# Output_block.net
KiCad netlist of a schematic drawn in Altium Designer
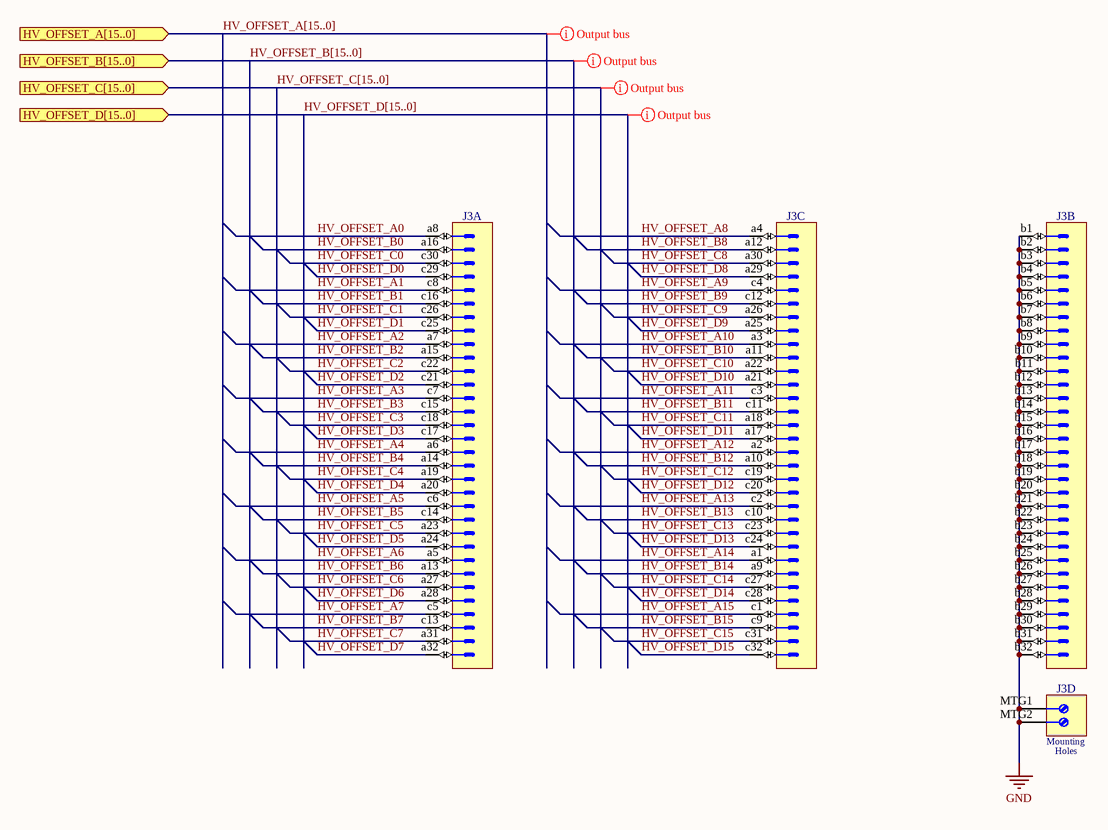
[diagram p0: Output_block.SchDoc]

(export (version "E")
  (design (tool "Eeschema 10.0.6"))
  (components
    (comp (ref "J3")
      (value "DIN 41612 Type C")
      (footprint "HARTING_09 03 696 6921")
      (description "Connector 96abc male (3x32)")
      (fields
        (field (name "PART NUMBER") "HARTING_09 03 696 6921")
        (field (name "MANUFACTURER") "HARTING")
        (field (name "AUTHOR") "CERN DEM JLC")
      )
      (libsource (lib "") (part "Connector 96abc male (3x32)_2"))
    )
  )
  (nets
    (net (code "1") (name "/HV_OFFSET_A0") (class "Default")
      (node (ref "J3") (pin "a8") (pinfunction "a8_a8") (pintype "bidirectional"))
    )
    (net (code "2") (name "/HV_OFFSET_A1") (class "Default")
      (node (ref "J3") (pin "c8") (pinfunction "c8_c8") (pintype "bidirectional"))
    )
    (net (code "3") (name "/HV_OFFSET_A2") (class "Default")
      (node (ref "J3") (pin "a7") (pinfunction "a7_a7") (pintype "bidirectional"))
    )
    (net (code "4") (name "/HV_OFFSET_A3") (class "Default")
      (node (ref "J3") (pin "c7") (pinfunction "c7_c7") (pintype "bidirectional"))
    )
    (net (code "5") (name "/HV_OFFSET_A4") (class "Default")
      (node (ref "J3") (pin "a6") (pinfunction "a6_a6") (pintype "bidirectional"))
    )
    (net (code "6") (name "/HV_OFFSET_A5") (class "Default")
      (node (ref "J3") (pin "c6") (pinfunction "c6_c6") (pintype "bidirectional"))
    )
    (net (code "7") (name "/HV_OFFSET_A6") (class "Default")
      (node (ref "J3") (pin "a5") (pinfunction "a5_a5") (pintype "bidirectional"))
    )
    (net (code "8") (name "/HV_OFFSET_A7") (class "Default")
      (node (ref "J3") (pin "c5") (pinfunction "c5_c5") (pintype "bidirectional"))
    )
    (net (code "9") (name "/HV_OFFSET_A8") (class "Default")
      (node (ref "J3") (pin "a4") (pinfunction "a4_a4") (pintype "bidirectional"))
    )
    (net (code "10") (name "/HV_OFFSET_A9") (class "Default")
      (node (ref "J3") (pin "c4") (pinfunction "c4_c4") (pintype "bidirectional"))
    )
    (net (code "11") (name "/HV_OFFSET_A10") (class "Default")
      (node (ref "J3") (pin "a3") (pinfunction "a3_a3") (pintype "bidirectional"))
    )
    (net (code "12") (name "/HV_OFFSET_A11") (class "Default")
      (node (ref "J3") (pin "c3") (pinfunction "c3_c3") (pintype "bidirectional"))
    )
    (net (code "13") (name "/HV_OFFSET_A12") (class "Default")
      (node (ref "J3") (pin "a2") (pinfunction "a2_a2") (pintype "bidirectional"))
    )
    (net (code "14") (name "/HV_OFFSET_A13") (class "Default")
      (node (ref "J3") (pin "c2") (pinfunction "c2_c2") (pintype "bidirectional"))
    )
    (net (code "15") (name "/HV_OFFSET_A14") (class "Default")
      (node (ref "J3") (pin "a1") (pinfunction "a1_a1") (pintype "bidirectional"))
    )
    (net (code "16") (name "/HV_OFFSET_A15") (class "Default")
      (node (ref "J3") (pin "c1") (pinfunction "c1_c1") (pintype "bidirectional"))
    )
    (net (code "18") (name "/HV_OFFSET_B0") (class "Default")
      (node (ref "J3") (pin "a16") (pinfunction "a16_a16") (pintype "bidirectional"))
    )
    (net (code "19") (name "/HV_OFFSET_B1") (class "Default")
      (node (ref "J3") (pin "c16") (pinfunction "c16_c16") (pintype "bidirectional"))
    )
    (net (code "20") (name "/HV_OFFSET_B2") (class "Default")
      (node (ref "J3") (pin "a15") (pinfunction "a15_a15") (pintype "bidirectional"))
    )
    (net (code "21") (name "/HV_OFFSET_B3") (class "Default")
      (node (ref "J3") (pin "c15") (pinfunction "c15_c15") (pintype "bidirectional"))
    )
    (net (code "22") (name "/HV_OFFSET_B4") (class "Default")
      (node (ref "J3") (pin "a14") (pinfunction "a14_a14") (pintype "bidirectional"))
    )
    (net (code "23") (name "/HV_OFFSET_B5") (class "Default")
      (node (ref "J3") (pin "c14") (pinfunction "c14_c14") (pintype "bidirectional"))
    )
    (net (code "24") (name "/HV_OFFSET_B6") (class "Default")
      (node (ref "J3") (pin "a13") (pinfunction "a13_a13") (pintype "bidirectional"))
    )
    (net (code "25") (name "/HV_OFFSET_B7") (class "Default")
      (node (ref "J3") (pin "c13") (pinfunction "c13_c13") (pintype "bidirectional"))
    )
    (net (code "26") (name "/HV_OFFSET_B8") (class "Default")
      (node (ref "J3") (pin "a12") (pinfunction "a12_a12") (pintype "bidirectional"))
    )
    (net (code "27") (name "/HV_OFFSET_B9") (class "Default")
      (node (ref "J3") (pin "c12") (pinfunction "c12_c12") (pintype "bidirectional"))
    )
    (net (code "28") (name "/HV_OFFSET_B10") (class "Default")
      (node (ref "J3") (pin "a11") (pinfunction "a11_a11") (pintype "bidirectional"))
    )
    (net (code "29") (name "/HV_OFFSET_B11") (class "Default")
      (node (ref "J3") (pin "c11") (pinfunction "c11_c11") (pintype "bidirectional"))
    )
    (net (code "30") (name "/HV_OFFSET_B12") (class "Default")
      (node (ref "J3") (pin "a10") (pinfunction "a10_a10") (pintype "bidirectional"))
    )
    (net (code "31") (name "/HV_OFFSET_B13") (class "Default")
      (node (ref "J3") (pin "c10") (pinfunction "c10_c10") (pintype "bidirectional"))
    )
    (net (code "32") (name "/HV_OFFSET_B14") (class "Default")
      (node (ref "J3") (pin "a9") (pinfunction "a9_a9") (pintype "bidirectional"))
    )
    (net (code "33") (name "/HV_OFFSET_B15") (class "Default")
      (node (ref "J3") (pin "c9") (pinfunction "c9_c9") (pintype "bidirectional"))
    )
    (net (code "35") (name "/HV_OFFSET_C0") (class "Default")
      (node (ref "J3") (pin "c30") (pinfunction "c30_c30") (pintype "bidirectional"))
    )
    (net (code "36") (name "/HV_OFFSET_C1") (class "Default")
      (node (ref "J3") (pin "c26") (pinfunction "c26_c26") (pintype "bidirectional"))
    )
    (net (code "37") (name "/HV_OFFSET_C2") (class "Default")
      (node (ref "J3") (pin "c22") (pinfunction "c22_c22") (pintype "bidirectional"))
    )
    (net (code "38") (name "/HV_OFFSET_C3") (class "Default")
      (node (ref "J3") (pin "c18") (pinfunction "c18_c18") (pintype "bidirectional"))
    )
    (net (code "39") (name "/HV_OFFSET_C4") (class "Default")
      (node (ref "J3") (pin "a19") (pinfunction "a19_a19") (pintype "bidirectional"))
    )
    (net (code "40") (name "/HV_OFFSET_C5") (class "Default")
      (node (ref "J3") (pin "a23") (pinfunction "a23_a23") (pintype "bidirectional"))
    )
    (net (code "41") (name "/HV_OFFSET_C6") (class "Default")
      (node (ref "J3") (pin "a27") (pinfunction "a27_a27") (pintype "bidirectional"))
    )
    (net (code "42") (name "/HV_OFFSET_C7") (class "Default")
      (node (ref "J3") (pin "a31") (pinfunction "a31_a31") (pintype "bidirectional"))
    )
    (net (code "43") (name "/HV_OFFSET_C8") (class "Default")
      (node (ref "J3") (pin "a30") (pinfunction "a30_a30") (pintype "bidirectional"))
    )
    (net (code "44") (name "/HV_OFFSET_C9") (class "Default")
      (node (ref "J3") (pin "a26") (pinfunction "a26_a26") (pintype "bidirectional"))
    )
    (net (code "45") (name "/HV_OFFSET_C10") (class "Default")
      (node (ref "J3") (pin "a22") (pinfunction "a22_a22") (pintype "bidirectional"))
    )
    (net (code "46") (name "/HV_OFFSET_C11") (class "Default")
      (node (ref "J3") (pin "a18") (pinfunction "a18_a18") (pintype "bidirectional"))
    )
    (net (code "47") (name "/HV_OFFSET_C12") (class "Default")
      (node (ref "J3") (pin "c19") (pinfunction "c19_c19") (pintype "bidirectional"))
    )
    (net (code "48") (name "/HV_OFFSET_C13") (class "Default")
      (node (ref "J3") (pin "c23") (pinfunction "c23_c23") (pintype "bidirectional"))
    )
    (net (code "49") (name "/HV_OFFSET_C14") (class "Default")
      (node (ref "J3") (pin "c27") (pinfunction "c27_c27") (pintype "bidirectional"))
    )
    (net (code "50") (name "/HV_OFFSET_C15") (class "Default")
      (node (ref "J3") (pin "c31") (pinfunction "c31_c31") (pintype "bidirectional"))
    )
    (net (code "52") (name "/HV_OFFSET_D0") (class "Default")
      (node (ref "J3") (pin "c29") (pinfunction "c29_c29") (pintype "bidirectional"))
    )
    (net (code "53") (name "/HV_OFFSET_D1") (class "Default")
      (node (ref "J3") (pin "c25") (pinfunction "c25_c25") (pintype "bidirectional"))
    )
    (net (code "54") (name "/HV_OFFSET_D2") (class "Default")
      (node (ref "J3") (pin "c21") (pinfunction "c21_c21") (pintype "bidirectional"))
    )
    (net (code "55") (name "/HV_OFFSET_D3") (class "Default")
      (node (ref "J3") (pin "c17") (pinfunction "c17_c17") (pintype "bidirectional"))
    )
    (net (code "56") (name "/HV_OFFSET_D4") (class "Default")
      (node (ref "J3") (pin "a20") (pinfunction "a20_a20") (pintype "bidirectional"))
    )
    (net (code "57") (name "/HV_OFFSET_D5") (class "Default")
      (node (ref "J3") (pin "a24") (pinfunction "a24_a24") (pintype "bidirectional"))
    )
    (net (code "58") (name "/HV_OFFSET_D6") (class "Default")
      (node (ref "J3") (pin "a28") (pinfunction "a28_a28") (pintype "bidirectional"))
    )
    (net (code "59") (name "/HV_OFFSET_D7") (class "Default")
      (node (ref "J3") (pin "a32") (pinfunction "a32_a32") (pintype "bidirectional"))
    )
    (net (code "60") (name "/HV_OFFSET_D8") (class "Default")
      (node (ref "J3") (pin "a29") (pinfunction "a29_a29") (pintype "bidirectional"))
    )
    (net (code "61") (name "/HV_OFFSET_D9") (class "Default")
      (node (ref "J3") (pin "a25") (pinfunction "a25_a25") (pintype "bidirectional"))
    )
    (net (code "62") (name "/HV_OFFSET_D10") (class "Default")
      (node (ref "J3") (pin "a21") (pinfunction "a21_a21") (pintype "bidirectional"))
    )
    (net (code "63") (name "/HV_OFFSET_D11") (class "Default")
      (node (ref "J3") (pin "a17") (pinfunction "a17_a17") (pintype "bidirectional"))
    )
    (net (code "64") (name "/HV_OFFSET_D12") (class "Default")
      (node (ref "J3") (pin "c20") (pinfunction "c20_c20") (pintype "bidirectional"))
    )
    (net (code "65") (name "/HV_OFFSET_D13") (class "Default")
      (node (ref "J3") (pin "c24") (pinfunction "c24_c24") (pintype "bidirectional"))
    )
    (net (code "66") (name "/HV_OFFSET_D14") (class "Default")
      (node (ref "J3") (pin "c28") (pinfunction "c28_c28") (pintype "bidirectional"))
    )
    (net (code "67") (name "/HV_OFFSET_D15") (class "Default")
      (node (ref "J3") (pin "c32") (pinfunction "c32_c32") (pintype "bidirectional"))
    )
    (net (code "69") (name "GND") (class "Default")
      (node (ref "J3") (pin "MTG1") (pinfunction "MTG1_MTG1") (pintype "passive"))
      (node (ref "J3") (pin "MTG2") (pinfunction "MTG2_MTG2") (pintype "passive"))
      (node (ref "J3") (pin "b1") (pinfunction "b1_b1") (pintype "bidirectional"))
      (node (ref "J3") (pin "b10") (pinfunction "b10_b10") (pintype "bidirectional"))
      (node (ref "J3") (pin "b11") (pinfunction "b11_b11") (pintype "bidirectional"))
      (node (ref "J3") (pin "b12") (pinfunction "b12_b12") (pintype "bidirectional"))
      (node (ref "J3") (pin "b13") (pinfunction "b13_b13") (pintype "bidirectional"))
      (node (ref "J3") (pin "b14") (pinfunction "b14_b14") (pintype "bidirectional"))
      (node (ref "J3") (pin "b15") (pinfunction "b15_b15") (pintype "bidirectional"))
      (node (ref "J3") (pin "b16") (pinfunction "b16_b16") (pintype "bidirectional"))
      (node (ref "J3") (pin "b17") (pinfunction "b17_b17") (pintype "bidirectional"))
      (node (ref "J3") (pin "b18") (pinfunction "b18_b18") (pintype "bidirectional"))
      (node (ref "J3") (pin "b19") (pinfunction "b19_b19") (pintype "bidirectional"))
      (node (ref "J3") (pin "b2") (pinfunction "b2_b2") (pintype "bidirectional"))
      (node (ref "J3") (pin "b20") (pinfunction "b20_b20") (pintype "bidirectional"))
      (node (ref "J3") (pin "b21") (pinfunction "b21_b21") (pintype "bidirectional"))
      (node (ref "J3") (pin "b22") (pinfunction "b22_b22") (pintype "bidirectional"))
      (node (ref "J3") (pin "b23") (pinfunction "b23_b23") (pintype "bidirectional"))
      (node (ref "J3") (pin "b24") (pinfunction "b24_b24") (pintype "bidirectional"))
      (node (ref "J3") (pin "b25") (pinfunction "b25_b25") (pintype "bidirectional"))
      (node (ref "J3") (pin "b26") (pinfunction "b26_b26") (pintype "bidirectional"))
      (node (ref "J3") (pin "b27") (pinfunction "b27_b27") (pintype "bidirectional"))
      (node (ref "J3") (pin "b28") (pinfunction "b28_b28") (pintype "bidirectional"))
      (node (ref "J3") (pin "b29") (pinfunction "b29_b29") (pintype "bidirectional"))
      (node (ref "J3") (pin "b3") (pinfunction "b3_b3") (pintype "bidirectional"))
      (node (ref "J3") (pin "b30") (pinfunction "b30_b30") (pintype "bidirectional"))
      (node (ref "J3") (pin "b31") (pinfunction "b31_b31") (pintype "bidirectional"))
      (node (ref "J3") (pin "b32") (pinfunction "b32_b32") (pintype "bidirectional"))
      (node (ref "J3") (pin "b4") (pinfunction "b4_b4") (pintype "bidirectional"))
      (node (ref "J3") (pin "b5") (pinfunction "b5_b5") (pintype "bidirectional"))
      (node (ref "J3") (pin "b6") (pinfunction "b6_b6") (pintype "bidirectional"))
      (node (ref "J3") (pin "b7") (pinfunction "b7_b7") (pintype "bidirectional"))
      (node (ref "J3") (pin "b8") (pinfunction "b8_b8") (pintype "bidirectional"))
      (node (ref "J3") (pin "b9") (pinfunction "b9_b9") (pintype "bidirectional"))
    )
  )
)
